# KeeWatch_Top_Level.net
KiCad netlist of a schematic drawn in Altium Designer
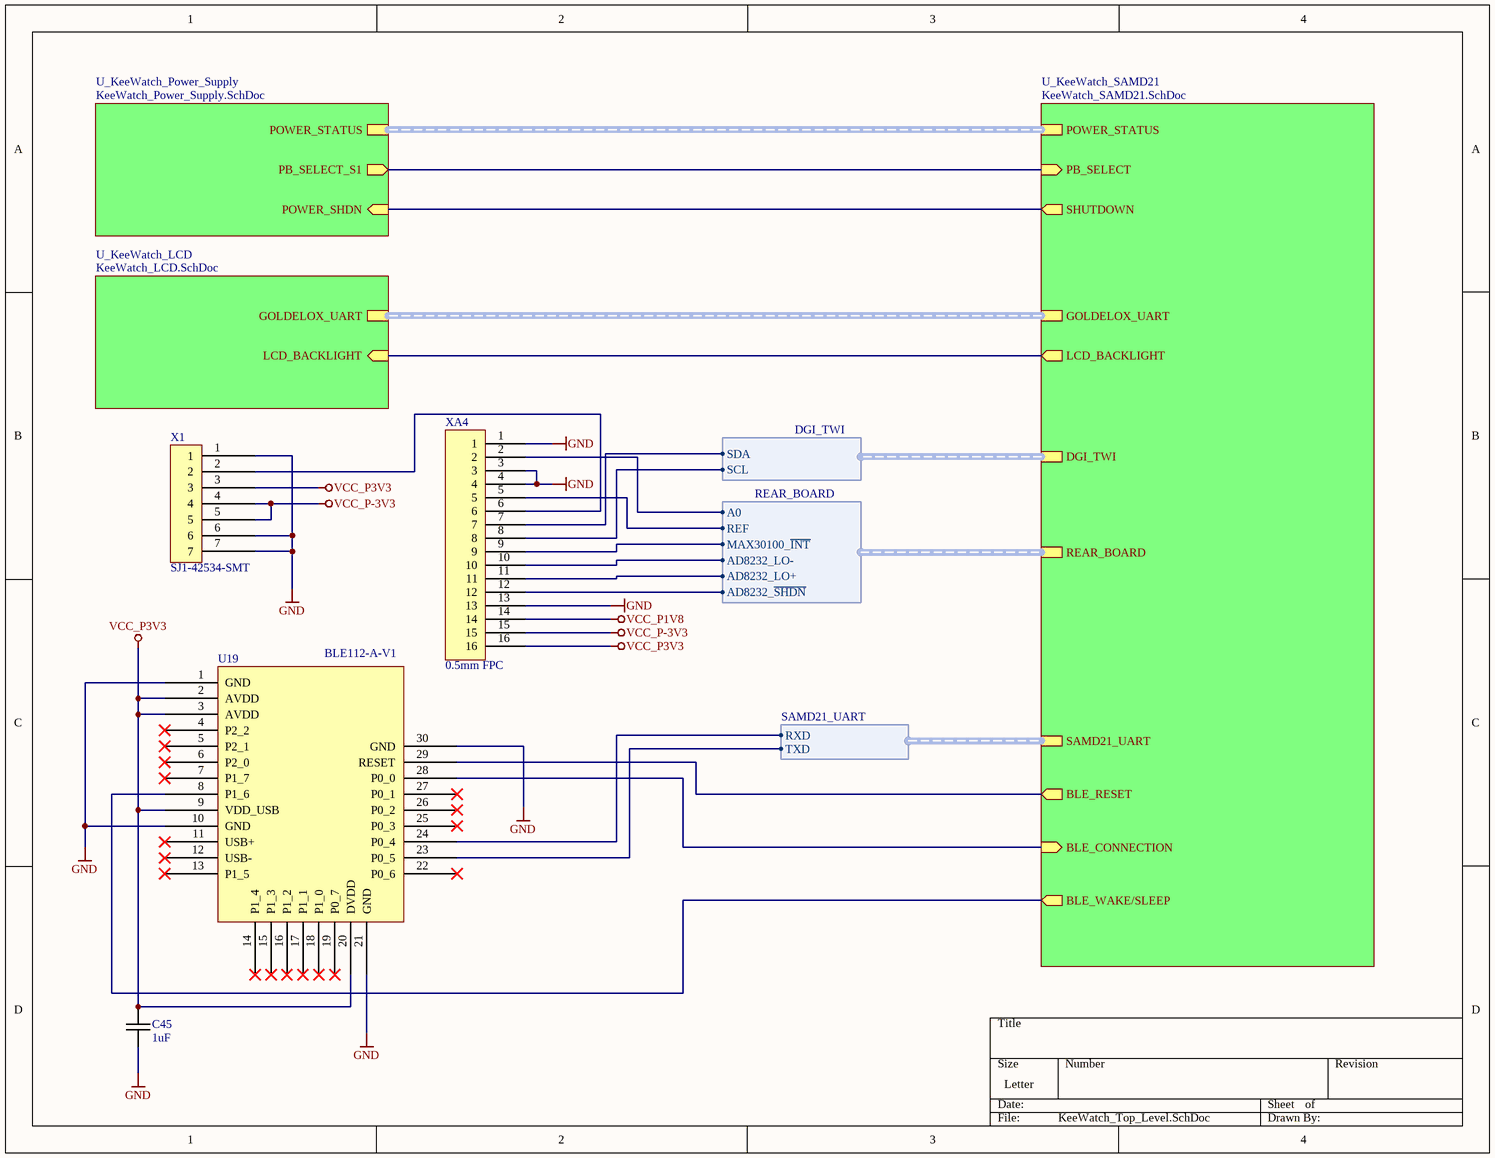
[diagram p0: KeeWatch_Top_Level.SchDoc]

(export (version "E")
  (design (tool "Eeschema 10.0.6"))
  (components
    (comp (ref "C45")
      (value "1uF")
      (footprint "0603-Cap")
      (description "CAPACITOR 0603 CERAMIC")
      (libsource (lib "Passives") (part "0603-Cap"))
    )
    (comp (ref "U19")
      (value "BLE112-A-V1")
      (footprint "BLE112-A-V1")
      (libsource (lib "Schlib2") (part "BLE112-A-V1"))
    )
    (comp (ref "X1")
      (value "SJ1-42534-SMT")
      (footprint "AUDIO_JACK")
      (description "2.5 MM AUDIO JACK")
      (libsource (lib "Schlib2") (part "SJ1-42534-SMT"))
    )
    (comp (ref "XA4")
      (value "0.5mm FPC")
      (footprint "16-PIN CONNECTOR")
      (description "0.5mm FPC 16-pin Connector")
      (libsource (lib "WATCH") (part "0.5mm FPC"))
    )
  )
  (nets
    (net (code "4") (name "/A0") (class "Default")
      (node (ref "XA4") (pin "2") (pinfunction "2_2") (pintype "passive"))
    )
    (net (code "5") (name "/AD8232_LO+") (class "Default")
      (node (ref "XA4") (pin "11") (pinfunction "11_11") (pintype "passive"))
    )
    (net (code "6") (name "/AD8232_LO-") (class "Default")
      (node (ref "XA4") (pin "10") (pinfunction "10_10") (pintype "passive"))
    )
    (net (code "7") (name "/AD8232_~{SHDN}") (class "Default")
      (node (ref "XA4") (pin "12") (pinfunction "12_12") (pintype "passive"))
    )
    (net (code "8") (name "/BLE_CONNECTION") (class "Default")
      (node (ref "U19") (pin "28") (pinfunction "P0_0_28") (pintype "passive"))
    )
    (net (code "9") (name "/BLE_RESET") (class "Default")
      (node (ref "U19") (pin "29") (pinfunction "RESET_29") (pintype "passive"))
    )
    (net (code "10") (name "/BLE_WAKE{slash}SLEEP") (class "Default")
      (node (ref "U19") (pin "8") (pinfunction "P1_6_8") (pintype "passive"))
    )
    (net (code "13") (name "/MAX30100_~{INT}") (class "Default")
      (node (ref "XA4") (pin "9") (pinfunction "9_9") (pintype "passive"))
    )
    (net (code "16") (name "/REF") (class "Default")
      (node (ref "XA4") (pin "5") (pinfunction "5_5") (pintype "passive"))
    )
    (net (code "17") (name "/RXD") (class "Default")
      (node (ref "U19") (pin "24") (pinfunction "P0_4_24") (pintype "passive"))
    )
    (net (code "18") (name "/SCL") (class "Default")
      (node (ref "XA4") (pin "8") (pinfunction "8_8") (pintype "passive"))
    )
    (net (code "19") (name "/SDA") (class "Default")
      (node (ref "XA4") (pin "7") (pinfunction "7_7") (pintype "passive"))
    )
    (net (code "21") (name "/TXD") (class "Default")
      (node (ref "U19") (pin "23") (pinfunction "P0_5_23") (pintype "passive"))
    )
    (net (code "25") (name "GND") (class "Default")
      (node (ref "C45") (pin "2") (pintype "passive"))
      (node (ref "U19") (pin "1") (pinfunction "GND_1") (pintype "passive"))
      (node (ref "U19") (pin "10") (pinfunction "GND_10") (pintype "passive"))
      (node (ref "U19") (pin "21") (pinfunction "GND_21") (pintype "passive"))
      (node (ref "U19") (pin "30") (pinfunction "GND_30") (pintype "passive"))
      (node (ref "X1") (pin "1") (pinfunction "1_1") (pintype "passive"))
      (node (ref "X1") (pin "6") (pinfunction "6_6") (pintype "passive"))
      (node (ref "X1") (pin "7") (pinfunction "7_7") (pintype "passive"))
      (node (ref "XA4") (pin "1") (pinfunction "1_1") (pintype "passive"))
      (node (ref "XA4") (pin "13") (pinfunction "13_13") (pintype "passive"))
      (node (ref "XA4") (pin "3") (pinfunction "3_3") (pintype "passive"))
      (node (ref "XA4") (pin "4") (pinfunction "4_4") (pintype "passive"))
    )
    (net (code "26") (name "Net-(X1-Pad2)") (class "Default")
      (node (ref "X1") (pin "2") (pinfunction "2_2") (pintype "passive"))
      (node (ref "XA4") (pin "6") (pinfunction "6_6") (pintype "passive"))
    )
    (net (code "27") (name "VCC_P-3V3") (class "Default")
      (node (ref "X1") (pin "4") (pinfunction "4_4") (pintype "passive"))
      (node (ref "X1") (pin "5") (pinfunction "5_5") (pintype "passive"))
      (node (ref "XA4") (pin "15") (pinfunction "15_15") (pintype "passive"))
    )
    (net (code "28") (name "VCC_P1V8") (class "Default")
      (node (ref "XA4") (pin "14") (pinfunction "14_14") (pintype "passive"))
    )
    (net (code "29") (name "VCC_P3V3") (class "Default")
      (node (ref "C45") (pin "1") (pintype "passive"))
      (node (ref "U19") (pin "2") (pinfunction "AVDD_2") (pintype "passive"))
      (node (ref "U19") (pin "20") (pinfunction "DVDD_20") (pintype "passive"))
      (node (ref "U19") (pin "3") (pinfunction "AVDD_3") (pintype "passive"))
      (node (ref "U19") (pin "9") (pinfunction "VDD_USB_9") (pintype "passive"))
      (node (ref "X1") (pin "3") (pinfunction "3_3") (pintype "passive"))
      (node (ref "XA4") (pin "16") (pinfunction "16_16") (pintype "passive"))
    )
    (net (code "30") (name "unconnected-(U19-P0_1-Pad27)") (class "Default")
      (node (ref "U19") (pin "27") (pinfunction "P0_1_27") (pintype "passive+no_connect"))
    )
    (net (code "31") (name "unconnected-(U19-P0_2-Pad26)") (class "Default")
      (node (ref "U19") (pin "26") (pinfunction "P0_2_26") (pintype "passive+no_connect"))
    )
    (net (code "32") (name "unconnected-(U19-P0_3-Pad25)") (class "Default")
      (node (ref "U19") (pin "25") (pinfunction "P0_3_25") (pintype "passive+no_connect"))
    )
    (net (code "33") (name "unconnected-(U19-P0_6-Pad22)") (class "Default")
      (node (ref "U19") (pin "22") (pinfunction "P0_6_22") (pintype "passive+no_connect"))
    )
    (net (code "34") (name "unconnected-(U19-P0_7-Pad19)") (class "Default")
      (node (ref "U19") (pin "19") (pinfunction "P0_7_19") (pintype "passive+no_connect"))
    )
    (net (code "35") (name "unconnected-(U19-P1_0-Pad18)") (class "Default")
      (node (ref "U19") (pin "18") (pinfunction "P1_0_18") (pintype "passive+no_connect"))
    )
    (net (code "36") (name "unconnected-(U19-P1_1-Pad17)") (class "Default")
      (node (ref "U19") (pin "17") (pinfunction "P1_1_17") (pintype "passive+no_connect"))
    )
    (net (code "37") (name "unconnected-(U19-P1_2-Pad16)") (class "Default")
      (node (ref "U19") (pin "16") (pinfunction "P1_2_16") (pintype "passive+no_connect"))
    )
    (net (code "38") (name "unconnected-(U19-P1_3-Pad15)") (class "Default")
      (node (ref "U19") (pin "15") (pinfunction "P1_3_15") (pintype "passive+no_connect"))
    )
    (net (code "39") (name "unconnected-(U19-P1_4-Pad14)") (class "Default")
      (node (ref "U19") (pin "14") (pinfunction "P1_4_14") (pintype "passive+no_connect"))
    )
    (net (code "40") (name "unconnected-(U19-P1_5-Pad13)") (class "Default")
      (node (ref "U19") (pin "13") (pinfunction "P1_5_13") (pintype "passive+no_connect"))
    )
    (net (code "41") (name "unconnected-(U19-P1_7-Pad7)") (class "Default")
      (node (ref "U19") (pin "7") (pinfunction "P1_7_7") (pintype "passive+no_connect"))
    )
    (net (code "42") (name "unconnected-(U19-P2_0-Pad6)") (class "Default")
      (node (ref "U19") (pin "6") (pinfunction "P2_0_6") (pintype "passive+no_connect"))
    )
    (net (code "43") (name "unconnected-(U19-P2_1-Pad5)") (class "Default")
      (node (ref "U19") (pin "5") (pinfunction "P2_1_5") (pintype "passive+no_connect"))
    )
    (net (code "44") (name "unconnected-(U19-P2_2-Pad4)") (class "Default")
      (node (ref "U19") (pin "4") (pinfunction "P2_2_4") (pintype "passive+no_connect"))
    )
    (net (code "45") (name "unconnected-(U19-USB+-Pad11)") (class "Default")
      (node (ref "U19") (pin "11") (pinfunction "USB+_11") (pintype "passive+no_connect"))
    )
    (net (code "46") (name "unconnected-(U19-USB--Pad12)") (class "Default")
      (node (ref "U19") (pin "12") (pinfunction "USB-_12") (pintype "passive+no_connect"))
    )
  )
)
